# NEO_Board.net
KiCad netlist of a schematic drawn in EAGLE
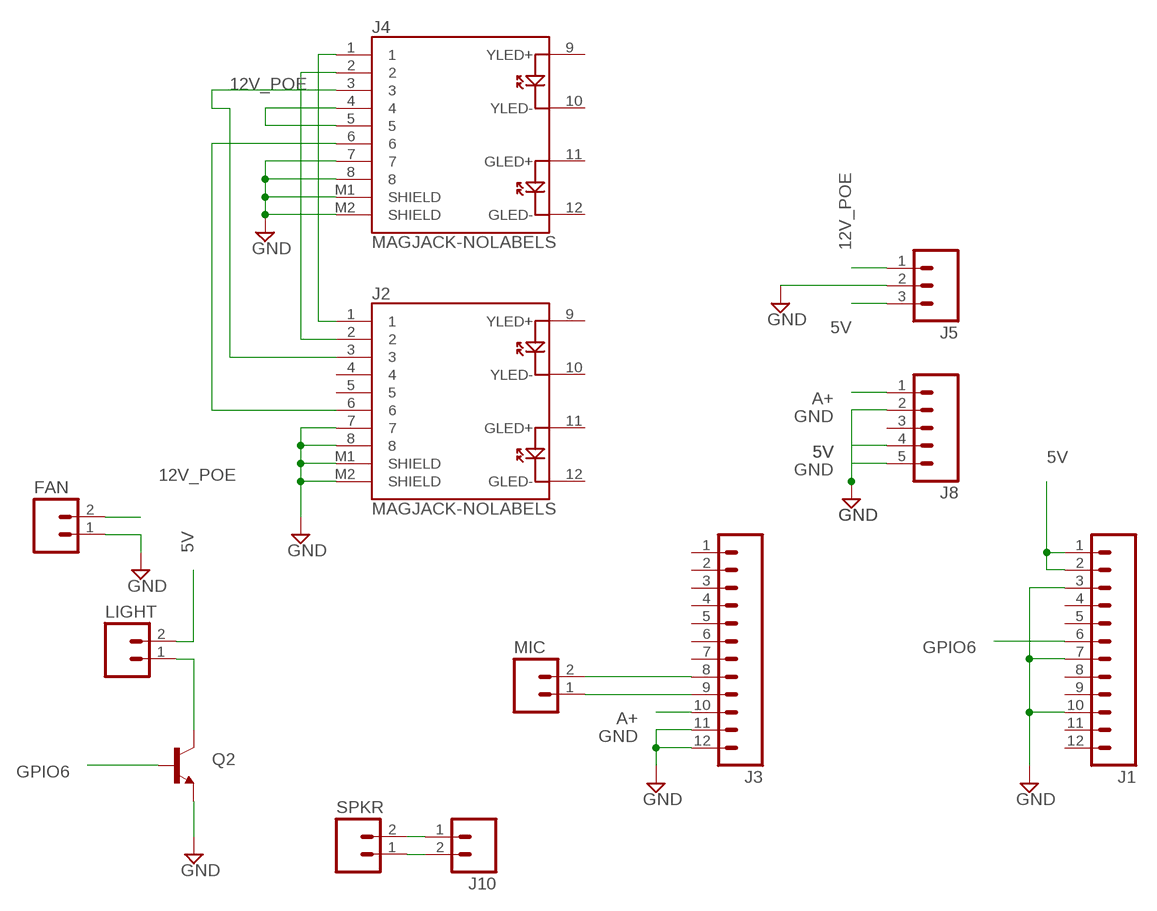
[diagram p0: schematic, sheet 1]

(export (version "E")
  (design (tool "Eeschema 10.0.6"))
  (components
    (comp (ref "FAN")
      (value "M02PTH")
      (footprint "eagle-import:1X02")
      (libsource (lib "eagle-import") (part "M02PTH"))
    )
    (comp (ref "J1")
      (value "M12PTH")
      (footprint "eagle-import:1X12")
      (libsource (lib "eagle-import") (part "M12PTH"))
    )
    (comp (ref "J2")
      (value "MAGJACK-NOLABELS")
      (footprint "eagle-import:MAGJACK")
      (libsource (lib "eagle-import") (part "MAGJACK-NOLABELS"))
    )
    (comp (ref "J3")
      (value "M12PTH")
      (footprint "eagle-import:1X12")
      (libsource (lib "eagle-import") (part "M12PTH"))
    )
    (comp (ref "J4")
      (value "MAGJACK-NOLABELS")
      (footprint "eagle-import:MAGJACK")
      (libsource (lib "eagle-import") (part "MAGJACK-NOLABELS"))
    )
    (comp (ref "J5")
      (value "M03PTH")
      (footprint "eagle-import:1X03")
      (libsource (lib "eagle-import") (part "M03PTH"))
    )
    (comp (ref "J8")
      (value "M05PTH")
      (footprint "eagle-import:1X05")
      (libsource (lib "eagle-import") (part "M05PTH"))
    )
    (comp (ref "J10")
      (value "M023.5MM")
      (footprint "eagle-import:SCREWTERMINAL-3.5MM-2")
      (libsource (lib "eagle-import") (part "M023.5MM"))
    )
    (comp (ref "LIGHT")
      (value "M02PTH")
      (footprint "eagle-import:1X02")
      (libsource (lib "eagle-import") (part "M02PTH"))
    )
    (comp (ref "MIC")
      (value "M02PTH")
      (footprint "eagle-import:1X02")
      (libsource (lib "eagle-import") (part "M02PTH"))
    )
    (comp (ref "Q2")
      (value "TRANSISTOR_NPNP2N2222A")
      (footprint "eagle-import:TO-92")
      (libsource (lib "eagle-import") (part "TRANSISTOR_NPNP2N2222A"))
    )
    (comp (ref "SPKR")
      (value "M02PTH")
      (footprint "eagle-import:1X02")
      (libsource (lib "eagle-import") (part "M02PTH"))
    )
  )
  (nets
    (net (code "1") (name "/5V") (class "Default")
      (node (ref "J1") (pin "1") (pinfunction "1_1") (pintype "passive"))
      (node (ref "J1") (pin "2") (pinfunction "2_2") (pintype "passive"))
      (node (ref "J5") (pin "3") (pinfunction "3_3") (pintype "passive"))
      (node (ref "J8") (pin "4") (pinfunction "4_4") (pintype "passive"))
      (node (ref "LIGHT") (pin "2") (pinfunction "2_2") (pintype "passive"))
    )
    (net (code "2") (name "/12V_POE") (class "Default")
      (node (ref "FAN") (pin "2") (pinfunction "2_2") (pintype "passive"))
      (node (ref "J4") (pin "4") (pinfunction "4_4") (pintype "bidirectional"))
      (node (ref "J4") (pin "5") (pinfunction "5_5") (pintype "bidirectional"))
      (node (ref "J5") (pin "1") (pinfunction "1_1") (pintype "passive"))
    )
    (net (code "3") (name "/A+") (class "Default")
      (node (ref "J3") (pin "10") (pinfunction "10_10") (pintype "passive"))
      (node (ref "J8") (pin "1") (pinfunction "1_1") (pintype "passive"))
    )
    (net (code "4") (name "/GPIO6") (class "Default")
      (node (ref "J1") (pin "6") (pinfunction "6_6") (pintype "passive"))
      (node (ref "Q2") (pin "2") (pinfunction "B_2") (pintype "passive"))
    )
    (net (code "5") (name "GND") (class "Default")
      (node (ref "FAN") (pin "1") (pinfunction "1_1") (pintype "passive"))
      (node (ref "J1") (pin "10") (pinfunction "10_10") (pintype "passive"))
      (node (ref "J1") (pin "3") (pinfunction "3_3") (pintype "passive"))
      (node (ref "J1") (pin "7") (pinfunction "7_7") (pintype "passive"))
      (node (ref "J2") (pin "7") (pinfunction "7_7") (pintype "bidirectional"))
      (node (ref "J2") (pin "8") (pinfunction "8_8") (pintype "bidirectional"))
      (node (ref "J2") (pin "M1") (pinfunction "SHIELD_M1") (pintype "bidirectional"))
      (node (ref "J2") (pin "M2") (pinfunction "SHIELD_M2") (pintype "bidirectional"))
      (node (ref "J3") (pin "11") (pinfunction "11_11") (pintype "passive"))
      (node (ref "J3") (pin "12") (pinfunction "12_12") (pintype "passive"))
      (node (ref "J4") (pin "7") (pinfunction "7_7") (pintype "bidirectional"))
      (node (ref "J4") (pin "8") (pinfunction "8_8") (pintype "bidirectional"))
      (node (ref "J4") (pin "M1") (pinfunction "SHIELD_M1") (pintype "bidirectional"))
      (node (ref "J4") (pin "M2") (pinfunction "SHIELD_M2") (pintype "bidirectional"))
      (node (ref "J5") (pin "2") (pinfunction "2_2") (pintype "passive"))
      (node (ref "J8") (pin "2") (pinfunction "2_2") (pintype "passive"))
      (node (ref "J8") (pin "5") (pinfunction "5_5") (pintype "passive"))
      (node (ref "Q2") (pin "3") (pinfunction "E_3") (pintype "passive"))
    )
    (net (code "6") (name "Net-(J2-Pad1)") (class "Default")
      (node (ref "J2") (pin "1") (pinfunction "1_1") (pintype "bidirectional"))
      (node (ref "J4") (pin "1") (pinfunction "1_1") (pintype "bidirectional"))
    )
    (net (code "7") (name "Net-(J2-Pad2)") (class "Default")
      (node (ref "J2") (pin "2") (pinfunction "2_2") (pintype "bidirectional"))
      (node (ref "J4") (pin "2") (pinfunction "2_2") (pintype "bidirectional"))
    )
    (net (code "8") (name "Net-(J2-Pad3)") (class "Default")
      (node (ref "J2") (pin "3") (pinfunction "3_3") (pintype "bidirectional"))
      (node (ref "J4") (pin "3") (pinfunction "3_3") (pintype "bidirectional"))
    )
    (net (code "9") (name "Net-(J2-Pad6)") (class "Default")
      (node (ref "J2") (pin "6") (pinfunction "6_6") (pintype "bidirectional"))
      (node (ref "J4") (pin "6") (pinfunction "6_6") (pintype "bidirectional"))
    )
    (net (code "10") (name "Net-(J3-Pad8)") (class "Default")
      (node (ref "J3") (pin "8") (pinfunction "8_8") (pintype "passive"))
      (node (ref "MIC") (pin "2") (pinfunction "2_2") (pintype "passive"))
    )
    (net (code "11") (name "Net-(J3-Pad9)") (class "Default")
      (node (ref "J3") (pin "9") (pinfunction "9_9") (pintype "passive"))
      (node (ref "MIC") (pin "1") (pinfunction "1_1") (pintype "passive"))
    )
    (net (code "12") (name "Net-(J10-Pad1)") (class "Default")
      (node (ref "J10") (pin "1") (pinfunction "1_1") (pintype "passive"))
      (node (ref "SPKR") (pin "2") (pinfunction "2_2") (pintype "passive"))
    )
    (net (code "13") (name "Net-(J10-Pad2)") (class "Default")
      (node (ref "J10") (pin "2") (pinfunction "2_2") (pintype "passive"))
      (node (ref "SPKR") (pin "1") (pinfunction "1_1") (pintype "passive"))
    )
    (net (code "14") (name "Net-(Q2-C)") (class "Default")
      (node (ref "LIGHT") (pin "1") (pinfunction "1_1") (pintype "passive"))
      (node (ref "Q2") (pin "1") (pinfunction "C_1") (pintype "passive"))
    )
    (net (code "15") (name "unconnected-(J1-Pad4)") (class "Default")
      (node (ref "J1") (pin "4") (pinfunction "4_4") (pintype "passive"))
    )
    (net (code "16") (name "unconnected-(J1-Pad5)") (class "Default")
      (node (ref "J1") (pin "5") (pinfunction "5_5") (pintype "passive"))
    )
    (net (code "17") (name "unconnected-(J1-Pad8)") (class "Default")
      (node (ref "J1") (pin "8") (pinfunction "8_8") (pintype "passive"))
    )
    (net (code "18") (name "unconnected-(J1-Pad9)") (class "Default")
      (node (ref "J1") (pin "9") (pinfunction "9_9") (pintype "passive"))
    )
    (net (code "19") (name "unconnected-(J1-Pad11)") (class "Default")
      (node (ref "J1") (pin "11") (pinfunction "11_11") (pintype "passive"))
    )
    (net (code "20") (name "unconnected-(J1-Pad12)") (class "Default")
      (node (ref "J1") (pin "12") (pinfunction "12_12") (pintype "passive"))
    )
    (net (code "21") (name "unconnected-(J2-GLED+-Pad11)") (class "Default")
      (node (ref "J2") (pin "11") (pinfunction "GLED+_11") (pintype "bidirectional"))
    )
    (net (code "22") (name "unconnected-(J2-GLED--Pad12)") (class "Default")
      (node (ref "J2") (pin "12") (pinfunction "GLED-_12") (pintype "bidirectional"))
    )
    (net (code "23") (name "unconnected-(J2-Pad4)") (class "Default")
      (node (ref "J2") (pin "4") (pinfunction "4_4") (pintype "bidirectional"))
    )
    (net (code "24") (name "unconnected-(J2-Pad5)") (class "Default")
      (node (ref "J2") (pin "5") (pinfunction "5_5") (pintype "bidirectional"))
    )
    (net (code "25") (name "unconnected-(J2-YLED+-Pad9)") (class "Default")
      (node (ref "J2") (pin "9") (pinfunction "YLED+_9") (pintype "bidirectional"))
    )
    (net (code "26") (name "unconnected-(J2-YLED--Pad10)") (class "Default")
      (node (ref "J2") (pin "10") (pinfunction "YLED-_10") (pintype "bidirectional"))
    )
    (net (code "27") (name "unconnected-(J3-Pad1)") (class "Default")
      (node (ref "J3") (pin "1") (pinfunction "1_1") (pintype "passive"))
    )
    (net (code "28") (name "unconnected-(J3-Pad2)") (class "Default")
      (node (ref "J3") (pin "2") (pinfunction "2_2") (pintype "passive"))
    )
    (net (code "29") (name "unconnected-(J3-Pad3)") (class "Default")
      (node (ref "J3") (pin "3") (pinfunction "3_3") (pintype "passive"))
    )
    (net (code "30") (name "unconnected-(J3-Pad4)") (class "Default")
      (node (ref "J3") (pin "4") (pinfunction "4_4") (pintype "passive"))
    )
    (net (code "31") (name "unconnected-(J3-Pad5)") (class "Default")
      (node (ref "J3") (pin "5") (pinfunction "5_5") (pintype "passive"))
    )
    (net (code "32") (name "unconnected-(J3-Pad6)") (class "Default")
      (node (ref "J3") (pin "6") (pinfunction "6_6") (pintype "passive"))
    )
    (net (code "33") (name "unconnected-(J3-Pad7)") (class "Default")
      (node (ref "J3") (pin "7") (pinfunction "7_7") (pintype "passive"))
    )
    (net (code "34") (name "unconnected-(J4-GLED+-Pad11)") (class "Default")
      (node (ref "J4") (pin "11") (pinfunction "GLED+_11") (pintype "bidirectional"))
    )
    (net (code "35") (name "unconnected-(J4-GLED--Pad12)") (class "Default")
      (node (ref "J4") (pin "12") (pinfunction "GLED-_12") (pintype "bidirectional"))
    )
    (net (code "36") (name "unconnected-(J4-YLED+-Pad9)") (class "Default")
      (node (ref "J4") (pin "9") (pinfunction "YLED+_9") (pintype "bidirectional"))
    )
    (net (code "37") (name "unconnected-(J4-YLED--Pad10)") (class "Default")
      (node (ref "J4") (pin "10") (pinfunction "YLED-_10") (pintype "bidirectional"))
    )
    (net (code "38") (name "unconnected-(J8-Pad3)") (class "Default")
      (node (ref "J8") (pin "3") (pinfunction "3_3") (pintype "passive"))
    )
  )
)
